# Battery_Fuel_Gauge.net
KiCad netlist of a schematic drawn in Altium Designer
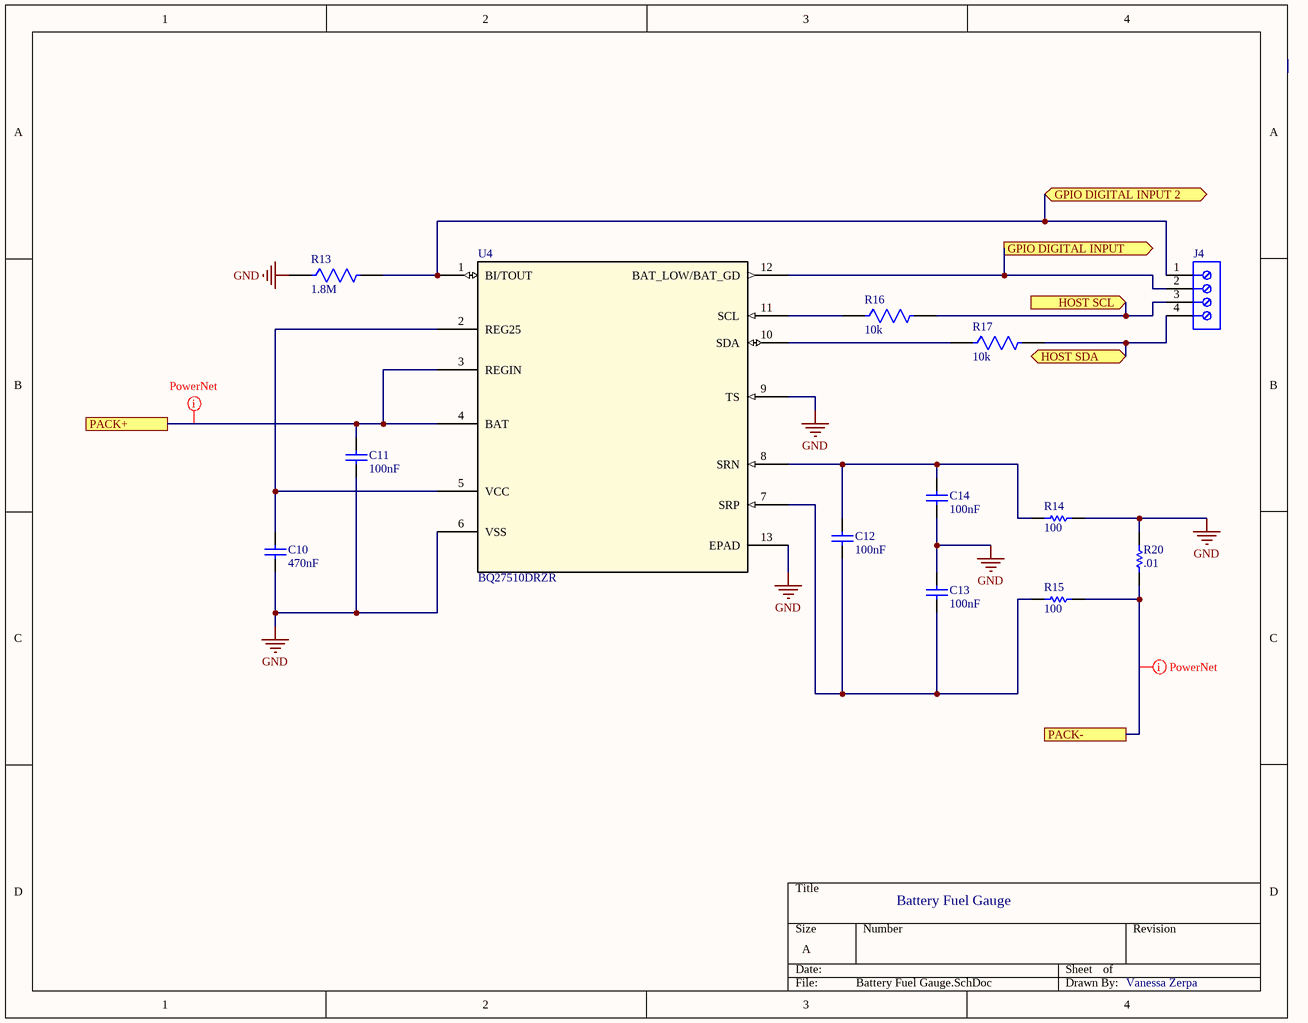
[diagram p0: Battery Fuel Gauge.SchDoc]

(export (version "E")
  (design (tool "Eeschema 10.0.6"))
  (components
    (comp (ref "C10")
      (value "470nF")
      (footprint "CAPC2013X140X50ML20T25")
      (fields
        (field (name "MANUFACTURER") "AVX Interconnect / Elco")
        (field (name "PART NUMBER") "08053D474KAT2A")
      )
      (libsource (lib "Altium Content Vault") (part "CAP"))
    )
    (comp (ref "C11")
      (value "100nF")
      (footprint "CAPC2013X94X50NL20T25")
      (fields
        (field (name "MANUFACTURER") "AVX Interconnect / Elco")
        (field (name "PART NUMBER") "08055C104KAT4A")
      )
      (libsource (lib "Altium Content Vault") (part "CAP"))
    )
    (comp (ref "C12")
      (value "100nF")
      (footprint "CAPC2013X94X50NL20T25")
      (fields
        (field (name "MANUFACTURER") "AVX Interconnect / Elco")
        (field (name "PART NUMBER") "08055C104KAT4A")
      )
      (libsource (lib "Altium Content Vault") (part "CAP"))
    )
    (comp (ref "C13")
      (value "100nF")
      (footprint "CAPC2013X94X50NL20T25")
      (fields
        (field (name "MANUFACTURER") "AVX Interconnect / Elco")
        (field (name "PART NUMBER") "08055C104KAT4A")
      )
      (libsource (lib "Altium Content Vault") (part "CAP"))
    )
    (comp (ref "C14")
      (value "100nF")
      (footprint "CAPC2013X94X50NL20T25")
      (fields
        (field (name "MANUFACTURER") "AVX Interconnect / Elco")
        (field (name "PART NUMBER") "08055C104KAT4A")
      )
      (libsource (lib "Altium Content Vault") (part "CAP"))
    )
    (comp (ref "J4")
      (value "Screw top terminal")
      (footprint "691709710304")
      (description "Serie 7097 - 5.00 mm Horizontal Entry SMT with Pressure Clamp WR-TBL, 4 pin")
      (fields
        (field (name "MANUFACTURER") "Wurth Elektronik")
        (field (name "PART NUMBER") "691709710304")
        (field (name "PUBLISHER") "WurthElektronik")
      )
      (libsource (lib "Altium Content Vault") (part "WE-CN-1P-F-TB4"))
    )
    (comp (ref "R13")
      (value "1.8M")
      (footprint "FP-CRCW0805-e3-MFG")
      (description "RES Thick Film, 1.8MΩ, 5%, 0.125W, 200ppm/°C, 0805")
      (fields (field (name "TOLERANCE") "5%"))
      (libsource (lib "Altium Content Vault") (part "1029c3af85768c4190bb7ad29bc67b5"))
    )
    (comp (ref "R14")
      (value "100")
      (footprint "RESC2013X60X40ML20T25")
      (fields (field (name "MANUFACTURER") "Panasonic") (field (name "PART NUMBER") "ERA6AEB101V"))
      (libsource (lib "Altium Content Vault") (part "RES"))
    )
    (comp (ref "R15")
      (value "100")
      (footprint "RESC2013X60X40ML20T25")
      (fields (field (name "MANUFACTURER") "Panasonic") (field (name "PART NUMBER") "ERA6AEB101V"))
      (libsource (lib "Altium Content Vault") (part "RES"))
    )
    (comp (ref "R16")
      (value "10k")
      (footprint "FP-CR0805-IPC_B")
      (description "Thick Film Chip Resistors 0805 10kΩ 0.125W 5% 200ppm/°C")
      (fields (field (name "TOLERANCE") "5%"))
      (libsource (lib "Altium Content Vault") (part "1029c3af85768c4190bb7ad29bc67b5"))
    )
    (comp (ref "R17")
      (value "10k")
      (footprint "FP-CR0805-IPC_B")
      (description "Thick Film Chip Resistors 0805 10kΩ 0.125W 5% 200ppm/°C")
      (fields (field (name "TOLERANCE") "5%"))
      (libsource (lib "Altium Content Vault") (part "1029c3af85768c4190bb7ad29bc67b5"))
    )
    (comp (ref "R20")
      (value ".01")
      (footprint "RESC2013X75X55NL20T20")
      (fields (field (name "PART NUMBER") "ERJ-6BWFR010V") (field (name "MANUFACTURER") "Panasonic"))
      (libsource (lib "Altium Content Vault") (part "RES"))
    )
    (comp (ref "U4")
      (value "BQ27510DRZR")
      (footprint "DRZ12_1P95X2P45")
      (description "No Description Available")
      (fields (field (name "COPYRIGHT") "Copyright (C) 2021 Ultra Librarian. All rights reserved."))
      (libsource (lib "BatteryFuelGauge") (part "BQ27510DRZR"))
    )
  )
  (nets
    (net (code "1") (name "/GPIO DIGITAL INPUT") (class "Default")
      (node (ref "J4") (pin "2") (pinfunction "2_2") (pintype "passive"))
      (node (ref "U4") (pin "12") (pinfunction "BAT_LOW/BAT_GD_12") (pintype "output"))
    )
    (net (code "2") (name "/GPIO DIGITAL INPUT 2") (class "Default")
      (node (ref "J4") (pin "1") (pinfunction "1_1") (pintype "passive"))
      (node (ref "R13") (pin "2") (pinfunction "2_2") (pintype "passive"))
      (node (ref "U4") (pin "1") (pinfunction "BI/TOUT_1") (pintype "bidirectional"))
    )
    (net (code "3") (name "/HOST SCL") (class "Default")
      (node (ref "J4") (pin "3") (pinfunction "3_3") (pintype "passive"))
      (node (ref "R16") (pin "2") (pinfunction "2_2") (pintype "passive"))
    )
    (net (code "4") (name "/HOST SDA") (class "Default")
      (node (ref "J4") (pin "4") (pinfunction "4_4") (pintype "passive"))
      (node (ref "R17") (pin "2") (pinfunction "2_2") (pintype "passive"))
    )
    (net (code "5") (name "/PACK+") (class "Default")
      (node (ref "C11") (pin "2") (pinfunction "2_2") (pintype "passive"))
      (node (ref "U4") (pin "3") (pinfunction "REGIN_3") (pintype "power_in"))
      (node (ref "U4") (pin "4") (pinfunction "BAT_4") (pintype "passive"))
    )
    (net (code "6") (name "/PACK-") (class "Default")
      (node (ref "R15") (pin "2") (pinfunction "2_2") (pintype "passive"))
      (node (ref "R20") (pin "1") (pinfunction "1_1") (pintype "passive"))
    )
    (net (code "7") (name "GND") (class "Default")
      (node (ref "C10") (pin "1") (pinfunction "1_1") (pintype "passive"))
      (node (ref "C11") (pin "1") (pinfunction "1_1") (pintype "passive"))
      (node (ref "C13") (pin "2") (pinfunction "2_2") (pintype "passive"))
      (node (ref "C14") (pin "1") (pinfunction "1_1") (pintype "passive"))
      (node (ref "R13") (pin "1") (pinfunction "1_1") (pintype "passive"))
      (node (ref "R14") (pin "2") (pinfunction "2_2") (pintype "passive"))
      (node (ref "R20") (pin "2") (pinfunction "2_2") (pintype "passive"))
      (node (ref "U4") (pin "13") (pinfunction "EPAD_13") (pintype "power_in"))
      (node (ref "U4") (pin "6") (pinfunction "VSS_6") (pintype "power_in"))
      (node (ref "U4") (pin "9") (pinfunction "TS_9") (pintype "input"))
    )
    (net (code "8") (name "Net-(U4-REG25)") (class "Default")
      (node (ref "C10") (pin "2") (pinfunction "2_2") (pintype "passive"))
      (node (ref "U4") (pin "2") (pinfunction "REG25_2") (pintype "power_in"))
      (node (ref "U4") (pin "5") (pinfunction "VCC_5") (pintype "power_in"))
    )
    (net (code "9") (name "Net-(U4-SCL)") (class "Default")
      (node (ref "R16") (pin "1") (pinfunction "1_1") (pintype "passive"))
      (node (ref "U4") (pin "11") (pinfunction "SCL_11") (pintype "input"))
    )
    (net (code "10") (name "Net-(U4-SDA)") (class "Default")
      (node (ref "R17") (pin "1") (pinfunction "1_1") (pintype "passive"))
      (node (ref "U4") (pin "10") (pinfunction "SDA_10") (pintype "bidirectional"))
    )
    (net (code "11") (name "Net-(U4-SRN)") (class "Default")
      (node (ref "C12") (pin "2") (pinfunction "2_2") (pintype "passive"))
      (node (ref "C14") (pin "2") (pinfunction "2_2") (pintype "passive"))
      (node (ref "R14") (pin "1") (pinfunction "1_1") (pintype "passive"))
      (node (ref "U4") (pin "8") (pinfunction "SRN_8") (pintype "input"))
    )
    (net (code "12") (name "Net-(U4-SRP)") (class "Default")
      (node (ref "C12") (pin "1") (pinfunction "1_1") (pintype "passive"))
      (node (ref "C13") (pin "1") (pinfunction "1_1") (pintype "passive"))
      (node (ref "R15") (pin "1") (pinfunction "1_1") (pintype "passive"))
      (node (ref "U4") (pin "7") (pinfunction "SRP_7") (pintype "input"))
    )
  )
)
